# Detect_IR.net
KiCad netlist of a schematic drawn in Altium Designer
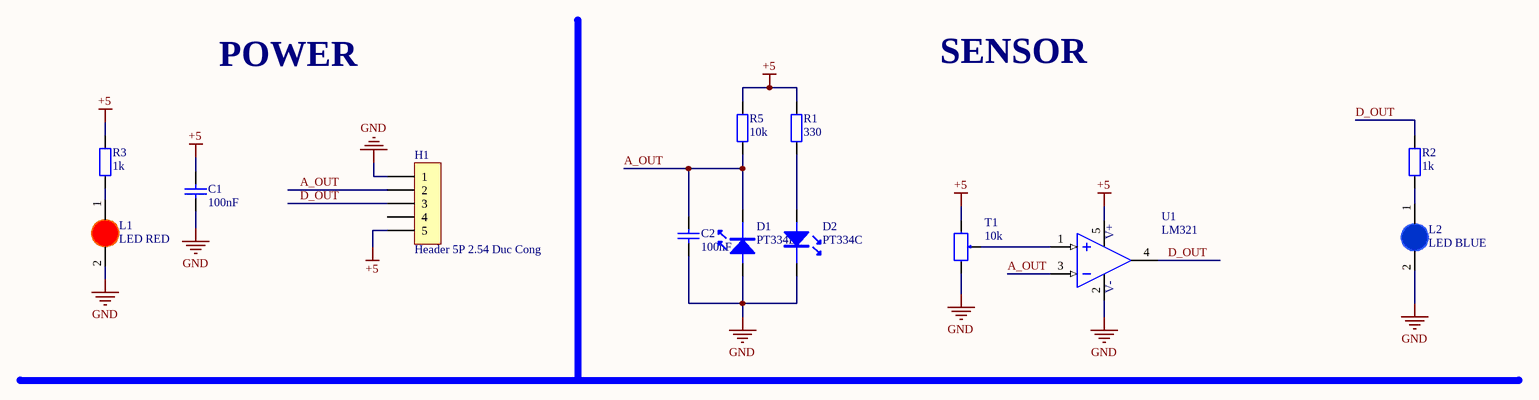
[diagram p0: Detect_IR.SchDoc]

(export (version "E")
  (design (tool "Eeschema 10.0.6"))
  (components
    (comp (ref "C1")
      (value "100nF")
      (footprint "tu 0603")
      (description "Dán")
      (libsource (lib "namnt_Lib") (part "Tu 0603 104 50V 10%"))
    )
    (comp (ref "C2")
      (value "100nF")
      (footprint "tu 0603")
      (description "Dán")
      (libsource (lib "namnt_Lib") (part "Tu 0603 104 50V 10%"))
    )
    (comp (ref "D1")
      (value "PT334B")
      (footprint "xlib:LED_CIRCLE_DIP_2P_5MM")
      (description "Led")
      (libsource (lib "XLib") (part "LED_DIP_2P"))
    )
    (comp (ref "D2")
      (value "PT334C")
      (footprint "xlib:LED_CIRCLE_DIP_2P_5MM")
      (description "Led")
      (libsource (lib "XLib") (part "LED_DIP_2P"))
    )
    (comp (ref "H1")
      (value "Header 5P 2.54 Duc Cong")
      (footprint "Header 5P DC 2.54")
      (description "Cắm")
      (libsource (lib "namnt_Lib") (part "Header 5P 2.54 Duc Cong"))
    )
    (comp (ref "L1")
      (value "LED RED")
      (footprint "LED-0805-Red")
      (description "Dán")
      (libsource (lib "namnt_Lib") (part "LED 0805 Do"))
    )
    (comp (ref "L2")
      (value "LED BLUE")
      (footprint "LED-0805-Blue")
      (description "Dán")
      (libsource (lib "namnt_Lib") (part "LED 0805 Xanh Duong"))
    )
    (comp (ref "R1")
      (value "330")
      (footprint "tro smd 0603")
      (description "Dán")
      (libsource (lib "namnt_Lib") (part "Tro 0603 1% 10k"))
    )
    (comp (ref "R2")
      (value "1k")
      (footprint "tro smd 0603")
      (description "Dán")
      (libsource (lib "namnt_Lib") (part "Tro 0603 1% 1k"))
    )
    (comp (ref "R3")
      (value "1k")
      (footprint "tro smd 0603")
      (description "Dán")
      (libsource (lib "namnt_Lib") (part "Tro 0603 1% 1k"))
    )
    (comp (ref "R5")
      (value "10k")
      (footprint "tro smd 0603")
      (description "Dán")
      (libsource (lib "namnt_Lib") (part "Tro 0603 1% 10k"))
    )
    (comp (ref "T1")
      (value "10k")
      (footprint "Bien Tro Vi Chinh Dung")
      (description "Cắm")
      (libsource (lib "namnt_Lib") (part "Bien Tro Tinh Chinh 10K Dung"))
    )
    (comp (ref "U1")
      (value "LM321")
      (footprint "xlib:sot23-5")
      (description "Opamp")
      (libsource (lib "XLib") (part "LM321"))
    )
  )
  (nets
    (net (code "1") (name "+5") (class "Default")
      (node (ref "C1") (pin "1") (pinfunction "1_1") (pintype "passive"))
      (node (ref "H1") (pin "5") (pinfunction "5_5") (pintype "passive"))
      (node (ref "R1") (pin "2") (pinfunction "2_2") (pintype "passive"))
      (node (ref "R3") (pin "2") (pinfunction "2_2") (pintype "passive"))
      (node (ref "R5") (pin "2") (pinfunction "2_2") (pintype "passive"))
      (node (ref "T1") (pin "3") (pinfunction "3_3") (pintype "passive"))
      (node (ref "U1") (pin "5") (pinfunction "V+_5") (pintype "power_in"))
    )
    (net (code "2") (name "/A_OUT") (class "Default")
      (node (ref "C2") (pin "1") (pinfunction "1_1") (pintype "passive"))
      (node (ref "D1") (pin "2") (pinfunction "2_2") (pintype "passive"))
      (node (ref "H1") (pin "2") (pinfunction "2_2") (pintype "passive"))
      (node (ref "R5") (pin "1") (pinfunction "1_1") (pintype "passive"))
      (node (ref "U1") (pin "3") (pinfunction "IN-_3") (pintype "input"))
    )
    (net (code "3") (name "/D_OUT") (class "Default")
      (node (ref "H1") (pin "3") (pinfunction "3_3") (pintype "passive"))
      (node (ref "R2") (pin "2") (pinfunction "2_2") (pintype "passive"))
      (node (ref "U1") (pin "4") (pinfunction "-V_4") (pintype "passive"))
    )
    (net (code "4") (name "GND") (class "Default")
      (node (ref "C1") (pin "2") (pinfunction "2_2") (pintype "passive"))
      (node (ref "C2") (pin "2") (pinfunction "2_2") (pintype "passive"))
      (node (ref "D1") (pin "1") (pinfunction "1_1") (pintype "passive"))
      (node (ref "D2") (pin "2") (pinfunction "2_2") (pintype "passive"))
      (node (ref "H1") (pin "1") (pinfunction "1_1") (pintype "passive"))
      (node (ref "L1") (pin "2") (pinfunction "K_2") (pintype "passive"))
      (node (ref "L2") (pin "2") (pinfunction "K_2") (pintype "passive"))
      (node (ref "T1") (pin "1") (pinfunction "1_1") (pintype "passive"))
      (node (ref "U1") (pin "2") (pinfunction "V-_2") (pintype "power_in"))
    )
    (net (code "5") (name "Net-(D2-Pad1)") (class "Default")
      (node (ref "D2") (pin "1") (pinfunction "1_1") (pintype "passive"))
      (node (ref "R1") (pin "1") (pinfunction "1_1") (pintype "passive"))
    )
    (net (code "6") (name "Net-(L1-A)") (class "Default")
      (node (ref "L1") (pin "1") (pinfunction "A_1") (pintype "passive"))
      (node (ref "R3") (pin "1") (pinfunction "1_1") (pintype "passive"))
    )
    (net (code "7") (name "Net-(L2-A)") (class "Default")
      (node (ref "L2") (pin "1") (pinfunction "A_1") (pintype "passive"))
      (node (ref "R2") (pin "1") (pinfunction "1_1") (pintype "passive"))
    )
    (net (code "8") (name "Net-(U1-IN+)") (class "Default")
      (node (ref "T1") (pin "2") (pinfunction "2_2") (pintype "passive"))
      (node (ref "U1") (pin "1") (pinfunction "IN+_1") (pintype "input"))
    )
    (net (code "9") (name "unconnected-(H1-Pad4)") (class "Default")
      (node (ref "H1") (pin "4") (pinfunction "4_4") (pintype "passive"))
    )
  )
)
